# LPCB235_-_BRAKE_FAILSAFE.net
KiCad netlist of a schematic drawn in Altium Designer
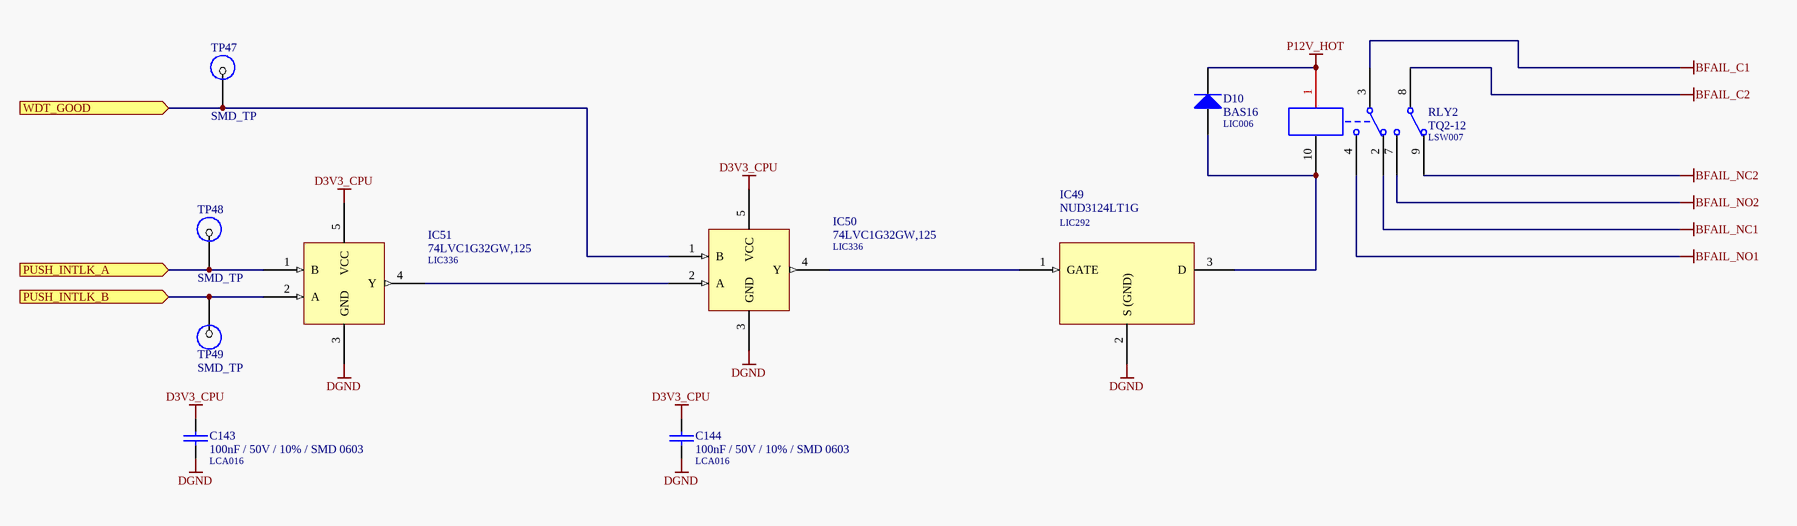
[diagram p0: LPCB235 - BRAKE FAILSAFE.SchDoc]

(export (version "E")
  (design (tool "Eeschema 10.0.6"))
  (components
    (comp (ref "C143")
      (value "100nF / 50V / 10% / SMD 0603")
      (footprint "LFP011__CC1608-0603-IPC7351_B")
      (description "Capacitor, Ceramic Chip, 100nF (0.1uF), 50V, 5%, SMD 0603 [LCA016]")
      (fields (field (name "LDL_NUMBER") "LCA016"))
      (libsource (lib "LDL_Capacitors") (part "100nF / 50V / 10% / SMD 0603"))
    )
    (comp (ref "C144")
      (value "100nF / 50V / 10% / SMD 0603")
      (footprint "LFP011__CC1608-0603-IPC7351_B")
      (description "Capacitor, Ceramic Chip, 100nF (0.1uF), 50V, 5%, SMD 0603 [LCA016]")
      (fields (field (name "LDL_NUMBER") "LCA016"))
      (libsource (lib "LDL_Capacitors") (part "100nF / 50V / 10% / SMD 0603"))
    )
    (comp (ref "D10")
      (value "BAS16")
      (footprint "LFP021__SOT23")
      (description "Diode, Small Signal, 0.2A, 85V, SMD SOT-23 [LIC006]")
      (fields (field (name "LDL_NUMBER") "LIC006"))
      (libsource (lib "LDL_Semiconductors") (part "BAS16"))
    )
    (comp (ref "IC49")
      (value "NUD3124LT1G")
      (footprint "LFP021__SOT23")
      (description "IC, Relay Driver, 28V Industrial, SMD SOT23 [LIC292]")
      (fields (field (name "LDL_NUMBER") "LIC292"))
      (libsource (lib "LDL_Semiconductors") (part "NUD3124LT1G"))
    )
    (comp (ref "IC50")
      (value "74LVC1G32GW,125")
      (footprint "LFP047__SOT353")
      (description "IC, Logic OR Gate, Single 2 Input, SMD SOT353 [LIC336]")
      (fields (field (name "LDL_NUMBER") "LIC336"))
      (libsource (lib "LDL_Semiconductors") (part "74LVC1G32GW,125"))
    )
    (comp (ref "IC51")
      (value "74LVC1G32GW,125")
      (footprint "LFP047__SOT353")
      (description "IC, Logic OR Gate, Single 2 Input, SMD SOT353 [LIC336]")
      (fields (field (name "LDL_NUMBER") "LIC336"))
      (libsource (lib "LDL_Semiconductors") (part "74LVC1G32GW,125"))
    )
    (comp (ref "RLY2")
      (value "TQ2-12")
      (footprint "TQ2")
      (description "Relay, DPDT, Non Latching, 12VDC Coil, 2A Rating, PTH")
      (fields (field (name "LDL_NUMBER") "LSW007"))
      (libsource (lib "LDL_Switching") (part "TQ2-12"))
    )
    (comp (ref "TP47")
      (value "SMD_TP")
      (footprint "SMD-TP")
      (description "SMD Test Point")
      (libsource (lib "LDL_Connectors") (part "SMD_TP"))
    )
    (comp (ref "TP48")
      (value "SMD_TP")
      (footprint "SMD-TP")
      (description "SMD Test Point")
      (libsource (lib "LDL_Connectors") (part "SMD_TP"))
    )
    (comp (ref "TP49")
      (value "SMD_TP")
      (footprint "SMD-TP")
      (description "SMD Test Point")
      (libsource (lib "LDL_Connectors") (part "SMD_TP"))
    )
  )
  (nets
    (net (code "1") (name "/PUSH_INTLK_A") (class "Default")
      (node (ref "IC51") (pin "1") (pinfunction "B_1") (pintype "input"))
      (node (ref "TP48") (pin "1") (pintype "passive"))
    )
    (net (code "2") (name "/PUSH_INTLK_B") (class "Default")
      (node (ref "IC51") (pin "2") (pinfunction "A_2") (pintype "input"))
      (node (ref "TP49") (pin "1") (pintype "passive"))
    )
    (net (code "3") (name "/WDT_GOOD") (class "Default")
      (node (ref "IC50") (pin "1") (pinfunction "B_1") (pintype "input"))
      (node (ref "TP47") (pin "1") (pintype "passive"))
    )
    (net (code "4") (name "BFAIL_C1") (class "Default")
      (node (ref "RLY2") (pin "3") (pinfunction "3_3") (pintype "passive"))
    )
    (net (code "5") (name "BFAIL_C2") (class "Default")
      (node (ref "RLY2") (pin "8") (pinfunction "8_8") (pintype "passive"))
    )
    (net (code "6") (name "BFAIL_NC1") (class "Default")
      (node (ref "RLY2") (pin "2") (pinfunction "2_2") (pintype "passive"))
    )
    (net (code "7") (name "BFAIL_NC2") (class "Default")
      (node (ref "RLY2") (pin "9") (pinfunction "9_9") (pintype "passive"))
    )
    (net (code "8") (name "BFAIL_NO1") (class "Default")
      (node (ref "RLY2") (pin "4") (pinfunction "4_4") (pintype "passive"))
    )
    (net (code "9") (name "BFAIL_NO2") (class "Default")
      (node (ref "RLY2") (pin "7") (pinfunction "7_7") (pintype "passive"))
    )
    (net (code "10") (name "D3V3_CPU") (class "Default")
      (node (ref "C143") (pin "1") (pintype "passive"))
      (node (ref "C144") (pin "1") (pintype "passive"))
      (node (ref "IC50") (pin "5") (pinfunction "VCC_5") (pintype "power_in"))
      (node (ref "IC51") (pin "5") (pinfunction "VCC_5") (pintype "power_in"))
    )
    (net (code "11") (name "DGND") (class "Default")
      (node (ref "C143") (pin "2") (pintype "passive"))
      (node (ref "C144") (pin "2") (pintype "passive"))
      (node (ref "IC49") (pin "2") (pinfunction "S_(GND)_2") (pintype "passive"))
      (node (ref "IC50") (pin "3") (pinfunction "GND_3") (pintype "power_in"))
      (node (ref "IC51") (pin "3") (pinfunction "GND_3") (pintype "power_in"))
    )
    (net (code "12") (name "Net-(D10-A)") (class "Default")
      (node (ref "D10") (pin "1") (pinfunction "A_1") (pintype "passive"))
      (node (ref "IC49") (pin "3") (pinfunction "D_3") (pintype "passive"))
      (node (ref "RLY2") (pin "10") (pinfunction "10_10") (pintype "passive"))
    )
    (net (code "13") (name "Net-(IC49-GATE)") (class "Default")
      (node (ref "IC49") (pin "1") (pinfunction "GATE_1") (pintype "input"))
      (node (ref "IC50") (pin "4") (pinfunction "Y_4") (pintype "output"))
    )
    (net (code "14") (name "Net-(IC50-A)") (class "Default")
      (node (ref "IC50") (pin "2") (pinfunction "A_2") (pintype "input"))
      (node (ref "IC51") (pin "4") (pinfunction "Y_4") (pintype "output"))
    )
    (net (code "15") (name "P12V_HOT") (class "Default")
      (node (ref "D10") (pin "3") (pinfunction "K_3") (pintype "passive"))
      (node (ref "RLY2") (pin "1") (pinfunction "1_1") (pintype "passive"))
    )
  )
)
